# LED_ZuTu-7_1.net
KiCad netlist of a schematic drawn in Altium Designer
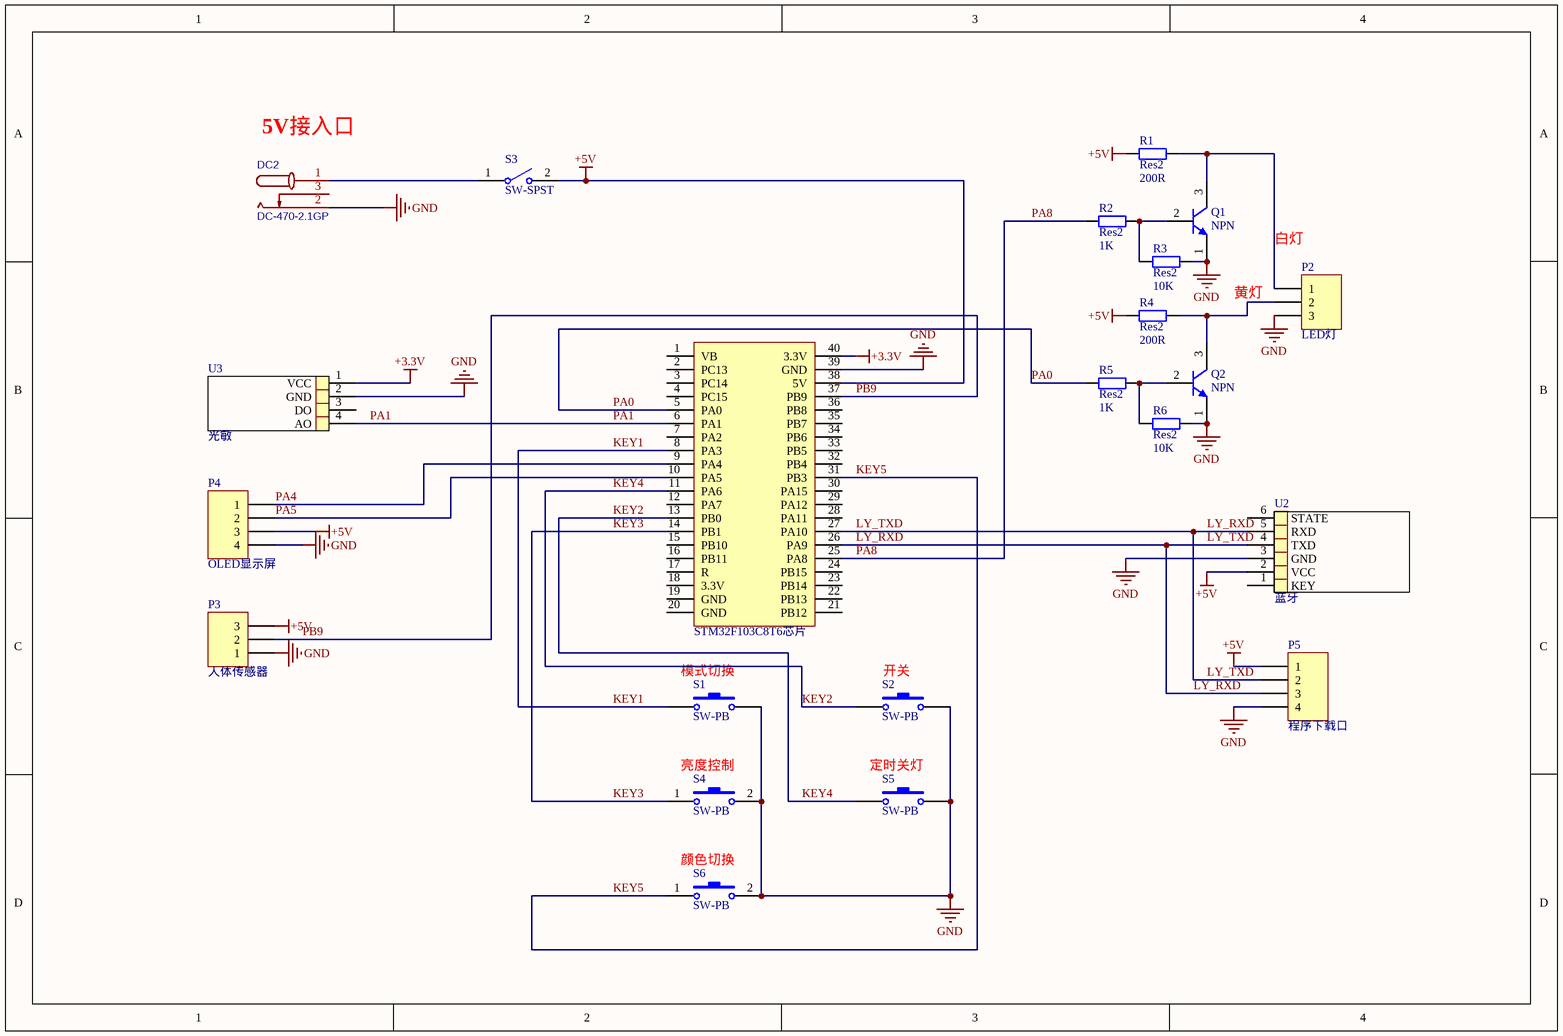
[diagram p0: LED_ZuTu-7.1.SchDoc]

(export (version "E")
  (design (tool "Eeschema 10.0.6"))
  (components
    (comp (ref "DC2")
      (value "DC-470-2.1GP")
      (footprint "Q_J:DC-470-2.1GP - duplicate")
      (fields (field (name "BOM_SUPPLIER PART") "C194407") (field (name "CONTRIBUTOR") "LCSC"))
      (libsource (lib "Q_J") (part "DC-470-2.1GP"))
    )
    (comp (ref "P2")
      (value "LED灯")
      (footprint "HDR1X3")
      (description "Header, 3-Pin")
      (fields (field (name "PUBLISHER") "Altium Limited"))
      (libsource (lib "Miscellaneous Connectors") (part "Header 3"))
    )
    (comp (ref "P3")
      (value "人体传感器")
      (footprint "HDR1X3")
      (description "Header, 3-Pin")
      (fields (field (name "PUBLISHER") "Altium Limited"))
      (libsource (lib "") (part "Header 3_1"))
    )
    (comp (ref "P4")
      (value "OLED显示屏")
      (footprint "HDR1X4")
      (description "Header, 4-Pin")
      (fields (field (name "PUBLISHER") "Altium Limited"))
      (libsource (lib "Miscellaneous Connectors") (part "Header 4"))
    )
    (comp (ref "P5")
      (value "程序下载口")
      (footprint "HDR1X4")
      (description "Header, 4-Pin")
      (fields (field (name "PUBLISHER") "Altium Limited"))
      (libsource (lib "") (part "Header 4_1"))
    )
    (comp (ref "Q1")
      (value "NPN")
      (footprint "Q_J:SOT-23R")
      (description "NPN Bipolar Transistor")
      (fields (field (name "PUBLISHER") "Altium Limited"))
      (libsource (lib "Miscellaneous Devices") (part "NPN"))
    )
    (comp (ref "Q2")
      (value "NPN")
      (footprint "Q_J:SOT-23R")
      (description "NPN Bipolar Transistor")
      (fields (field (name "PUBLISHER") "Altium Limited"))
      (libsource (lib "Miscellaneous Devices") (part "NPN"))
    )
    (comp (ref "R1")
      (value "Res2")
      (footprint "Q_J:0805")
      (description "贴片电阻8050")
      (fields (field (name "ALTIUM_VALUE") "200R") (field (name "PUBLISHER") "Altium Limited"))
      (libsource (lib "Miscellaneous Devices") (part "Res2"))
    )
    (comp (ref "R2")
      (value "Res2")
      (footprint "Q_J:0805")
      (description "贴片电阻8050")
      (fields (field (name "ALTIUM_VALUE") "1K") (field (name "PUBLISHER") "Altium Limited"))
      (libsource (lib "Miscellaneous Devices") (part "Res2"))
    )
    (comp (ref "R3")
      (value "Res2")
      (footprint "Q_J:0805")
      (description "贴片电阻8050")
      (fields (field (name "ALTIUM_VALUE") "10K") (field (name "PUBLISHER") "Altium Limited"))
      (libsource (lib "Miscellaneous Devices") (part "Res2"))
    )
    (comp (ref "R4")
      (value "Res2")
      (footprint "Q_J:0805")
      (description "贴片电阻8050")
      (fields (field (name "ALTIUM_VALUE") "200R") (field (name "PUBLISHER") "Altium Limited"))
      (libsource (lib "Miscellaneous Devices") (part "Res2"))
    )
    (comp (ref "R5")
      (value "Res2")
      (footprint "Q_J:0805")
      (description "贴片电阻8050")
      (fields (field (name "ALTIUM_VALUE") "1K") (field (name "PUBLISHER") "Altium Limited"))
      (libsource (lib "Miscellaneous Devices") (part "Res2"))
    )
    (comp (ref "R6")
      (value "Res2")
      (footprint "Q_J:0805")
      (description "贴片电阻8050")
      (fields (field (name "ALTIUM_VALUE") "10K") (field (name "PUBLISHER") "Altium Limited"))
      (libsource (lib "Miscellaneous Devices") (part "Res2"))
    )
    (comp (ref "S1")
      (value "SW-PB")
      (footprint "Q_J:KEY_M")
      (description "Switch")
      (fields (field (name "PUBLISHER") "Altium Limited"))
      (libsource (lib "") (part "SW-PB_1"))
    )
    (comp (ref "S2")
      (value "SW-PB")
      (footprint "Q_J:KEY_M")
      (description "Switch")
      (fields (field (name "PUBLISHER") "Altium Limited"))
      (libsource (lib "") (part "SW-PB_1"))
    )
    (comp (ref "S3")
      (value "SW-SPST")
      (footprint "Q_J:BTN8.5*8.5")
      (description "Single-Pole, Single-Throw Switch")
      (fields (field (name "PUBLISHER") "Altium Limited"))
      (libsource (lib "Miscellaneous Devices") (part "SW-SPST"))
    )
    (comp (ref "S4")
      (value "SW-PB")
      (footprint "Q_J:KEY_M")
      (description "Switch")
      (fields (field (name "PUBLISHER") "Altium Limited"))
      (libsource (lib "Miscellaneous Devices") (part "SW-PB"))
    )
    (comp (ref "S5")
      (value "SW-PB")
      (footprint "Q_J:KEY_M")
      (description "Switch")
      (fields (field (name "PUBLISHER") "Altium Limited"))
      (libsource (lib "") (part "SW-PB_1"))
    )
    (comp (ref "S6")
      (value "SW-PB")
      (footprint "Q_J:KEY_M")
      (description "Switch")
      (fields (field (name "PUBLISHER") "Altium Limited"))
      (libsource (lib "Miscellaneous Devices") (part "SW-PB"))
    )
    (comp (ref "STM32F103C8T6芯片")
      (value "stm32f103c8t6_Board")
      (footprint "stm32-port")
      (description "MCU")
      (libsource (lib "Q_J") (part "stm32f103c8t6_Board"))
    )
    (comp (ref "U2") (value "蓝牙") (footprint "HDR1X6") (libsource (lib "Q_J") (part "LY")))
    (comp (ref "U3") (value "光敏") (footprint "HDR1X4") (libsource (lib "Q_J") (part "GM")))
  )
  (nets
    (net (code "1") (name "+3.3V") (class "Default")
      (node (ref "STM32F103C8T6芯片") (pin "40") (pinfunction "3.3V_40") (pintype "passive"))
      (node (ref "U3") (pin "1") (pinfunction "VCC_1") (pintype "passive"))
    )
    (net (code "2") (name "+5V") (class "Default")
      (node (ref "P3") (pin "3") (pinfunction "3_3") (pintype "passive"))
      (node (ref "P4") (pin "3") (pinfunction "3_3") (pintype "passive"))
      (node (ref "P5") (pin "1") (pinfunction "1_1") (pintype "passive"))
      (node (ref "R1") (pin "1") (pinfunction "1_1") (pintype "passive"))
      (node (ref "R4") (pin "1") (pinfunction "1_1") (pintype "passive"))
      (node (ref "S3") (pin "2") (pinfunction "NO_2") (pintype "passive"))
      (node (ref "STM32F103C8T6芯片") (pin "38") (pinfunction "5V_38") (pintype "passive"))
      (node (ref "U2") (pin "2") (pinfunction "VCC_2") (pintype "passive"))
    )
    (net (code "3") (name "/KEY1") (class "Default")
      (node (ref "S1") (pin "1") (pinfunction "1_1") (pintype "passive"))
      (node (ref "STM32F103C8T6芯片") (pin "8") (pinfunction "PA3_8") (pintype "passive"))
    )
    (net (code "4") (name "/KEY2") (class "Default")
      (node (ref "S2") (pin "1") (pinfunction "1_1") (pintype "passive"))
      (node (ref "S5") (pin "1") (pinfunction "1_1") (pintype "passive"))
      (node (ref "STM32F103C8T6芯片") (pin "11") (pinfunction "PA6_11") (pintype "passive"))
      (node (ref "STM32F103C8T6芯片") (pin "13") (pinfunction "PB0_13") (pintype "passive"))
    )
    (net (code "5") (name "/KEY3") (class "Default")
      (node (ref "S4") (pin "1") (pinfunction "1_1") (pintype "passive"))
      (node (ref "STM32F103C8T6芯片") (pin "14") (pinfunction "PB1_14") (pintype "passive"))
    )
    (net (code "6") (name "/KEY5") (class "Default")
      (node (ref "S6") (pin "1") (pinfunction "1_1") (pintype "passive"))
      (node (ref "STM32F103C8T6芯片") (pin "31") (pinfunction "PB3_31") (pintype "passive"))
    )
    (net (code "7") (name "/LY_RXD") (class "Default")
      (node (ref "P5") (pin "2") (pinfunction "2_2") (pintype "passive"))
      (node (ref "P5") (pin "3") (pinfunction "3_3") (pintype "passive"))
      (node (ref "STM32F103C8T6芯片") (pin "26") (pinfunction "PA9_26") (pintype "passive"))
      (node (ref "STM32F103C8T6芯片") (pin "27") (pinfunction "PA10_27") (pintype "passive"))
      (node (ref "U2") (pin "4") (pinfunction "TXD_4") (pintype "passive"))
      (node (ref "U2") (pin "5") (pinfunction "RXD_5") (pintype "passive"))
    )
    (net (code "8") (name "/PA0") (class "Default")
      (node (ref "R5") (pin "1") (pinfunction "1_1") (pintype "passive"))
      (node (ref "STM32F103C8T6芯片") (pin "5") (pinfunction "PA0_5") (pintype "passive"))
    )
    (net (code "9") (name "/PA1") (class "Default")
      (node (ref "STM32F103C8T6芯片") (pin "6") (pinfunction "PA1_6") (pintype "passive"))
      (node (ref "U3") (pin "4") (pinfunction "AO_4") (pintype "passive"))
    )
    (net (code "10") (name "/PA4") (class "Default")
      (node (ref "P4") (pin "1") (pinfunction "1_1") (pintype "passive"))
      (node (ref "STM32F103C8T6芯片") (pin "9") (pinfunction "PA4_9") (pintype "passive"))
    )
    (net (code "11") (name "/PA5") (class "Default")
      (node (ref "P4") (pin "2") (pinfunction "2_2") (pintype "passive"))
      (node (ref "STM32F103C8T6芯片") (pin "10") (pinfunction "PA5_10") (pintype "passive"))
    )
    (net (code "12") (name "/PA8") (class "Default")
      (node (ref "R2") (pin "1") (pinfunction "1_1") (pintype "passive"))
      (node (ref "STM32F103C8T6芯片") (pin "25") (pinfunction "PA8_25") (pintype "passive"))
    )
    (net (code "13") (name "/PB9") (class "Default")
      (node (ref "P3") (pin "2") (pinfunction "2_2") (pintype "passive"))
      (node (ref "STM32F103C8T6芯片") (pin "37") (pinfunction "PB9_37") (pintype "passive"))
    )
    (net (code "14") (name "GND") (class "Default")
      (node (ref "DC2") (pin "2") (pinfunction "2_2") (pintype "passive"))
      (node (ref "P2") (pin "3") (pinfunction "3_3") (pintype "passive"))
      (node (ref "P3") (pin "1") (pinfunction "1_1") (pintype "passive"))
      (node (ref "P4") (pin "4") (pinfunction "4_4") (pintype "passive"))
      (node (ref "P5") (pin "4") (pinfunction "4_4") (pintype "passive"))
      (node (ref "Q1") (pin "1") (pinfunction "E_1") (pintype "passive"))
      (node (ref "Q2") (pin "1") (pinfunction "E_1") (pintype "passive"))
      (node (ref "R3") (pin "2") (pinfunction "2_2") (pintype "passive"))
      (node (ref "R6") (pin "2") (pinfunction "2_2") (pintype "passive"))
      (node (ref "S1") (pin "2") (pinfunction "2_2") (pintype "passive"))
      (node (ref "S2") (pin "2") (pinfunction "2_2") (pintype "passive"))
      (node (ref "S4") (pin "2") (pinfunction "2_2") (pintype "passive"))
      (node (ref "S5") (pin "2") (pinfunction "2_2") (pintype "passive"))
      (node (ref "S6") (pin "2") (pinfunction "2_2") (pintype "passive"))
      (node (ref "STM32F103C8T6芯片") (pin "39") (pinfunction "GND_39") (pintype "passive"))
      (node (ref "U2") (pin "3") (pinfunction "GND_3") (pintype "passive"))
      (node (ref "U3") (pin "2") (pinfunction "GND_2") (pintype "passive"))
    )
    (net (code "15") (name "Net-(Q1-B)") (class "Default")
      (node (ref "Q1") (pin "2") (pinfunction "B_2") (pintype "passive"))
      (node (ref "R2") (pin "2") (pinfunction "2_2") (pintype "passive"))
      (node (ref "R3") (pin "1") (pinfunction "1_1") (pintype "passive"))
    )
    (net (code "16") (name "Net-(Q1-C)") (class "Default")
      (node (ref "P2") (pin "1") (pinfunction "1_1") (pintype "passive"))
      (node (ref "Q1") (pin "3") (pinfunction "C_3") (pintype "passive"))
      (node (ref "R1") (pin "2") (pinfunction "2_2") (pintype "passive"))
    )
    (net (code "17") (name "Net-(Q2-B)") (class "Default")
      (node (ref "Q2") (pin "2") (pinfunction "B_2") (pintype "passive"))
      (node (ref "R5") (pin "2") (pinfunction "2_2") (pintype "passive"))
      (node (ref "R6") (pin "1") (pinfunction "1_1") (pintype "passive"))
    )
    (net (code "18") (name "Net-(Q2-C)") (class "Default")
      (node (ref "P2") (pin "2") (pinfunction "2_2") (pintype "passive"))
      (node (ref "Q2") (pin "3") (pinfunction "C_3") (pintype "passive"))
      (node (ref "R4") (pin "2") (pinfunction "2_2") (pintype "passive"))
    )
    (net (code "19") (name "Net-(S3-COMMON)") (class "Default")
      (node (ref "DC2") (pin "1") (pinfunction "1_1") (pintype "passive"))
      (node (ref "S3") (pin "1") (pinfunction "COMMON_1") (pintype "passive"))
    )
    (net (code "20") (name "unconnected-(DC2-Pad3)") (class "Default")
      (node (ref "DC2") (pin "3") (pinfunction "3_3") (pintype "passive"))
    )
    (net (code "21") (name "unconnected-(STM32F103C8T6芯片-3.3V-Pad18)") (class "Default")
      (node (ref "STM32F103C8T6芯片") (pin "18") (pinfunction "3.3V_18") (pintype "passive"))
    )
    (net (code "22") (name "unconnected-(STM32F103C8T6芯片-GND-Pad19)") (class "Default")
      (node (ref "STM32F103C8T6芯片") (pin "19") (pinfunction "GND_19") (pintype "passive"))
    )
    (net (code "23") (name "unconnected-(STM32F103C8T6芯片-GND-Pad20)") (class "Default")
      (node (ref "STM32F103C8T6芯片") (pin "20") (pinfunction "GND_20") (pintype "passive"))
    )
    (net (code "24") (name "unconnected-(STM32F103C8T6芯片-PA2-Pad7)") (class "Default")
      (node (ref "STM32F103C8T6芯片") (pin "7") (pinfunction "PA2_7") (pintype "passive"))
    )
    (net (code "25") (name "unconnected-(STM32F103C8T6芯片-PA7-Pad12)") (class "Default")
      (node (ref "STM32F103C8T6芯片") (pin "12") (pinfunction "PA7_12") (pintype "passive"))
    )
    (net (code "26") (name "unconnected-(STM32F103C8T6芯片-PA11-Pad28)") (class "Default")
      (node (ref "STM32F103C8T6芯片") (pin "28") (pinfunction "PA11_28") (pintype "passive"))
    )
    (net (code "27") (name "unconnected-(STM32F103C8T6芯片-PA12-Pad29)") (class "Default")
      (node (ref "STM32F103C8T6芯片") (pin "29") (pinfunction "PA12_29") (pintype "passive"))
    )
    (net (code "28") (name "unconnected-(STM32F103C8T6芯片-PA15-Pad30)") (class "Default")
      (node (ref "STM32F103C8T6芯片") (pin "30") (pinfunction "PA15_30") (pintype "passive"))
    )
    (net (code "29") (name "unconnected-(STM32F103C8T6芯片-PB4-Pad32)") (class "Default")
      (node (ref "STM32F103C8T6芯片") (pin "32") (pinfunction "PB4_32") (pintype "passive"))
    )
    (net (code "30") (name "unconnected-(STM32F103C8T6芯片-PB5-Pad33)") (class "Default")
      (node (ref "STM32F103C8T6芯片") (pin "33") (pinfunction "PB5_33") (pintype "passive"))
    )
    (net (code "31") (name "unconnected-(STM32F103C8T6芯片-PB6-Pad34)") (class "Default")
      (node (ref "STM32F103C8T6芯片") (pin "34") (pinfunction "PB6_34") (pintype "passive"))
    )
    (net (code "32") (name "unconnected-(STM32F103C8T6芯片-PB7-Pad35)") (class "Default")
      (node (ref "STM32F103C8T6芯片") (pin "35") (pinfunction "PB7_35") (pintype "passive"))
    )
    (net (code "33") (name "unconnected-(STM32F103C8T6芯片-PB8-Pad36)") (class "Default")
      (node (ref "STM32F103C8T6芯片") (pin "36") (pinfunction "PB8_36") (pintype "passive"))
    )
    (net (code "34") (name "unconnected-(STM32F103C8T6芯片-PB10-Pad15)") (class "Default")
      (node (ref "STM32F103C8T6芯片") (pin "15") (pinfunction "PB10_15") (pintype "passive"))
    )
    (net (code "35") (name "unconnected-(STM32F103C8T6芯片-PB11-Pad16)") (class "Default")
      (node (ref "STM32F103C8T6芯片") (pin "16") (pinfunction "PB11_16") (pintype "passive"))
    )
    (net (code "36") (name "unconnected-(STM32F103C8T6芯片-PB12-Pad21)") (class "Default")
      (node (ref "STM32F103C8T6芯片") (pin "21") (pinfunction "PB12_21") (pintype "passive"))
    )
    (net (code "37") (name "unconnected-(STM32F103C8T6芯片-PB13-Pad22)") (class "Default")
      (node (ref "STM32F103C8T6芯片") (pin "22") (pinfunction "PB13_22") (pintype "passive"))
    )
    (net (code "38") (name "unconnected-(STM32F103C8T6芯片-PB14-Pad23)") (class "Default")
      (node (ref "STM32F103C8T6芯片") (pin "23") (pinfunction "PB14_23") (pintype "passive"))
    )
    (net (code "39") (name "unconnected-(STM32F103C8T6芯片-PB15-Pad24)") (class "Default")
      (node (ref "STM32F103C8T6芯片") (pin "24") (pinfunction "PB15_24") (pintype "passive"))
    )
    (net (code "40") (name "unconnected-(STM32F103C8T6芯片-PC13-Pad2)") (class "Default")
      (node (ref "STM32F103C8T6芯片") (pin "2") (pinfunction "PC13_2") (pintype "passive"))
    )
    (net (code "41") (name "unconnected-(STM32F103C8T6芯片-PC14-Pad3)") (class "Default")
      (node (ref "STM32F103C8T6芯片") (pin "3") (pinfunction "PC14_3") (pintype "passive"))
    )
    (net (code "42") (name "unconnected-(STM32F103C8T6芯片-PC15-Pad4)") (class "Default")
      (node (ref "STM32F103C8T6芯片") (pin "4") (pinfunction "PC15_4") (pintype "passive"))
    )
    (net (code "43") (name "unconnected-(STM32F103C8T6芯片-R-Pad17)") (class "Default")
      (node (ref "STM32F103C8T6芯片") (pin "17") (pinfunction "R_17") (pintype "passive"))
    )
    (net (code "44") (name "unconnected-(STM32F103C8T6芯片-VB-Pad1)") (class "Default")
      (node (ref "STM32F103C8T6芯片") (pin "1") (pinfunction "VB_1") (pintype "passive"))
    )
    (net (code "45") (name "unconnected-(U2-KEY-Pad1)") (class "Default")
      (node (ref "U2") (pin "1") (pinfunction "KEY_1") (pintype "passive"))
    )
    (net (code "46") (name "unconnected-(U2-STATE-Pad6)") (class "Default")
      (node (ref "U2") (pin "6") (pinfunction "STATE_6") (pintype "passive"))
    )
    (net (code "47") (name "unconnected-(U3-DO-Pad3)") (class "Default")
      (node (ref "U3") (pin "3") (pinfunction "DO_3") (pintype "passive"))
    )
  )
)
